# LightLink_V4.net
KiCad netlist of a schematic drawn in Altium Designer
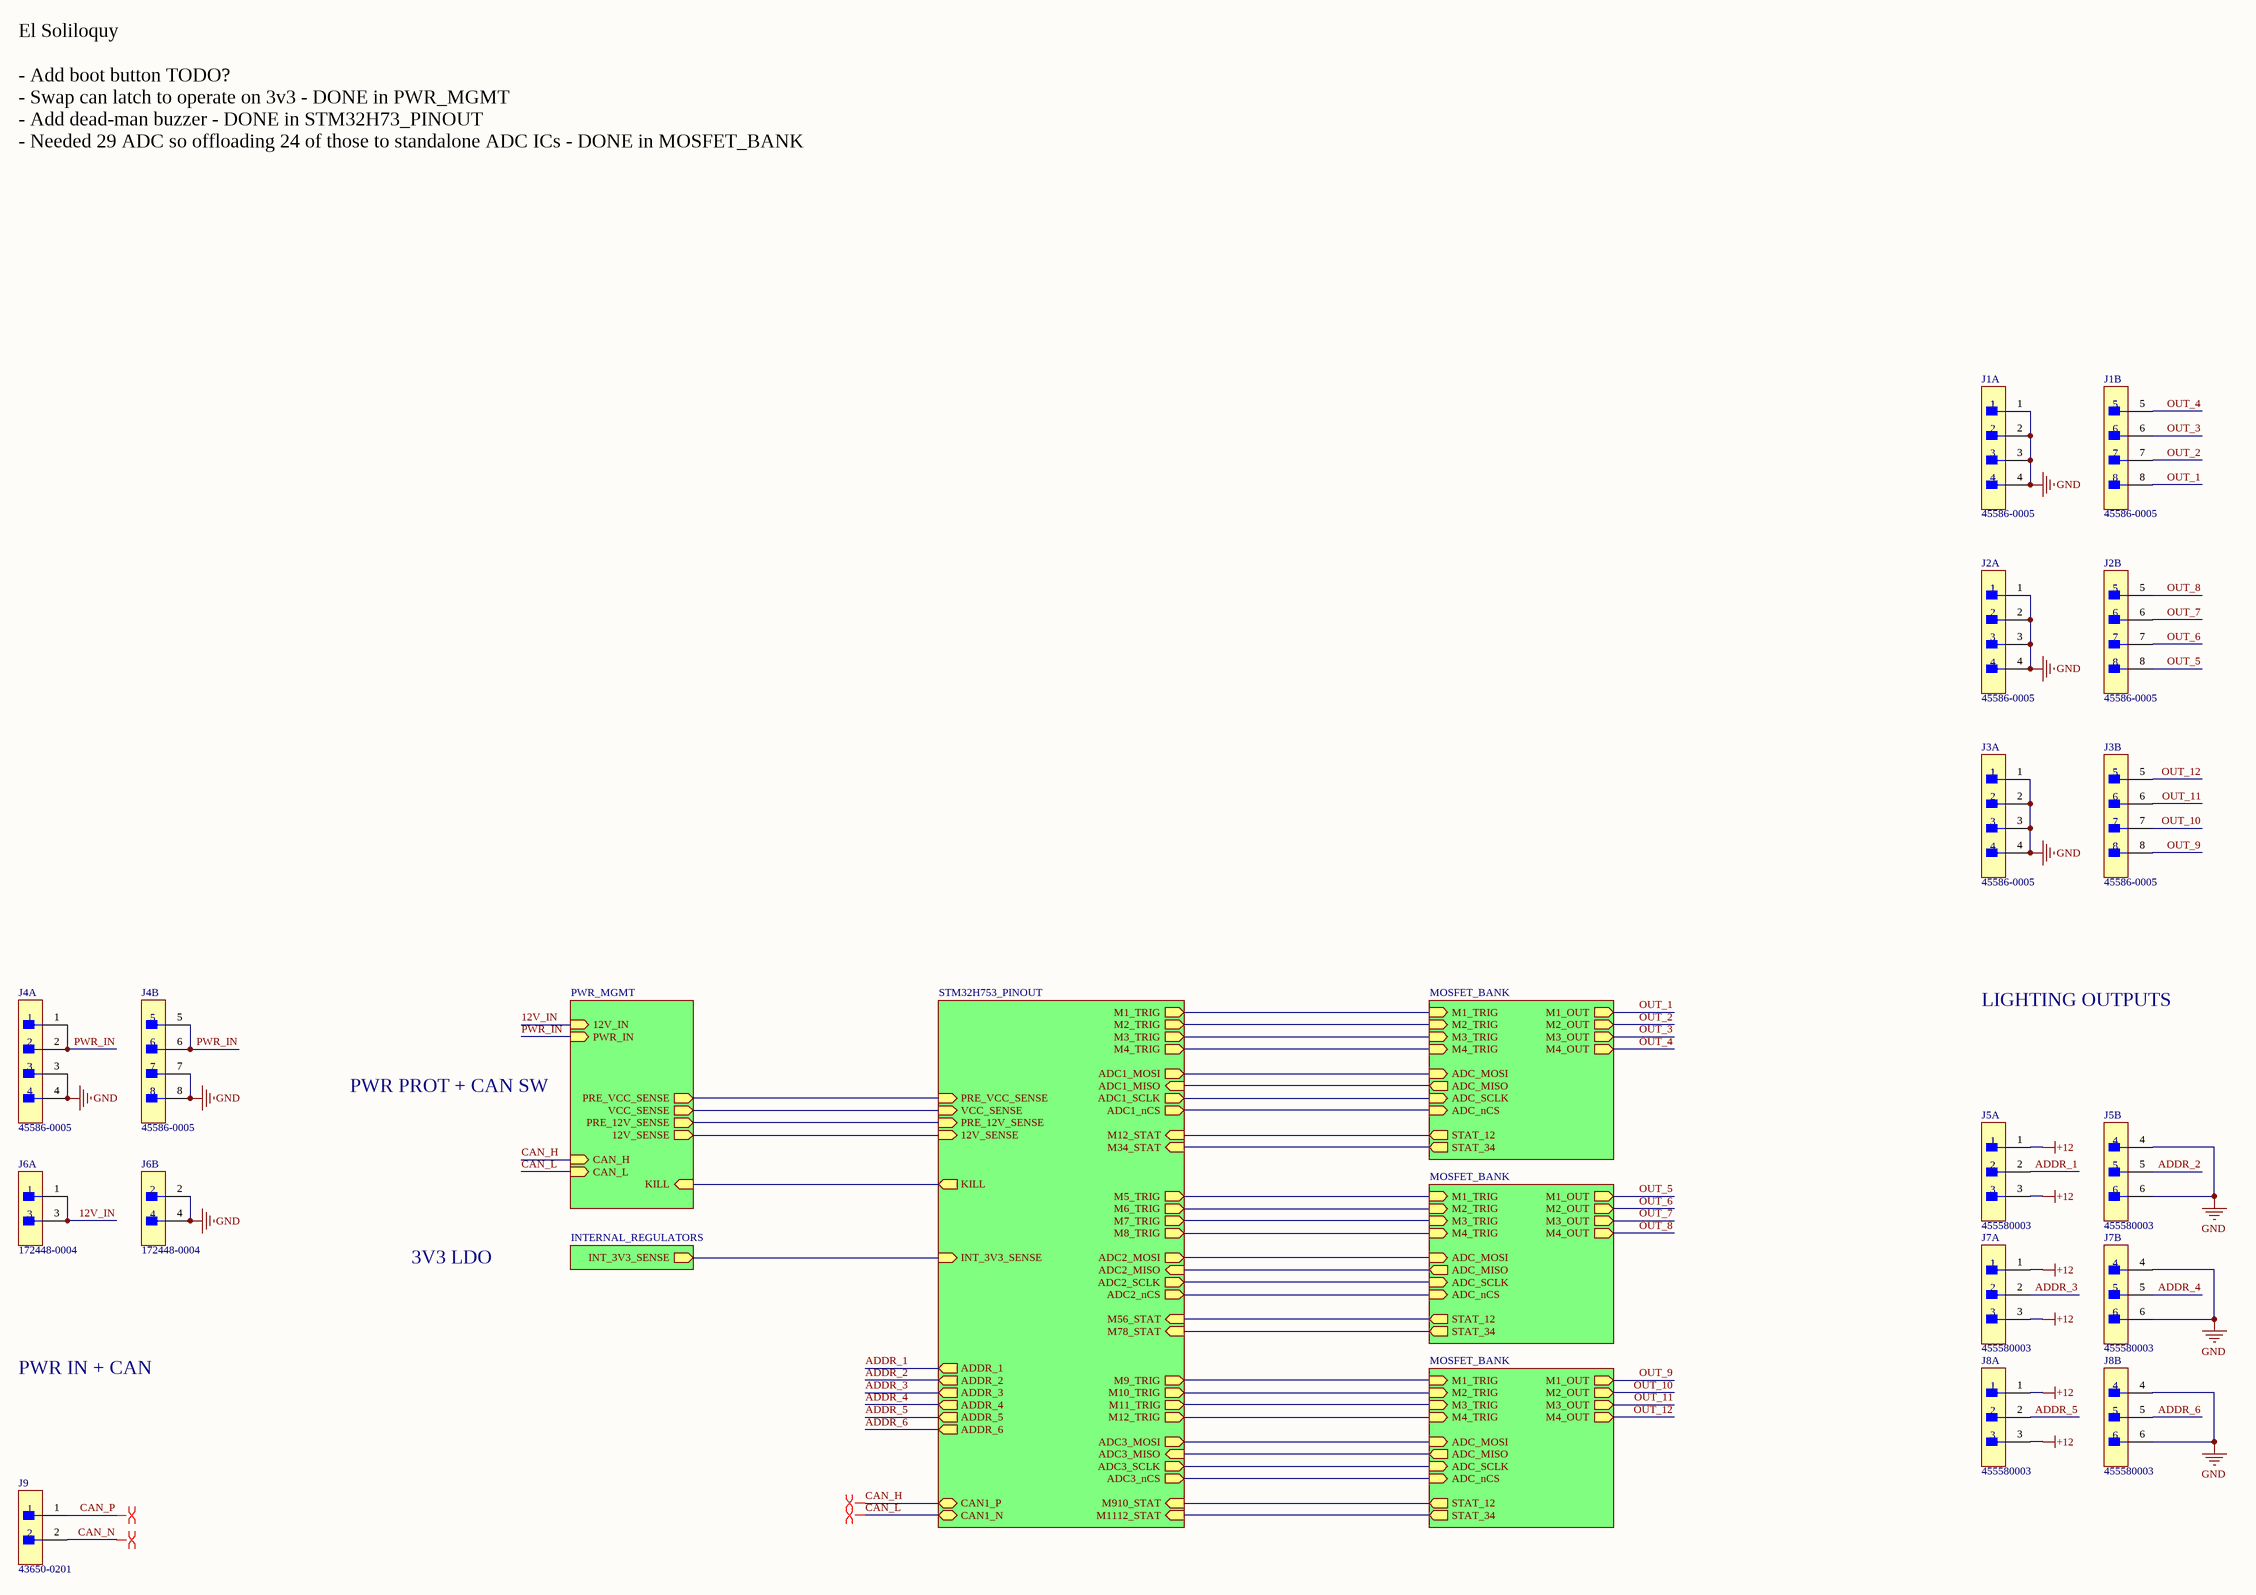
[diagram p0: LightLink_V4.SchDoc]

(export (version "E")
  (design (tool "Eeschema 10.0.6"))
  (components
    (comp (ref "J1")
      (value "45586-0005")
      (footprint "FP-45586-0005-MFG")
      (description "CONN HEADER R/A 8POS 4.2MM")
      (libsource (lib "Altium Content Vault") (part "85438c39ca9ef07d43bb2e97c52bc44"))
    )
    (comp (ref "J2")
      (value "45586-0005")
      (footprint "FP-45586-0005-MFG")
      (description "CONN HEADER R/A 8POS 4.2MM")
      (libsource (lib "Altium Content Vault") (part "85438c39ca9ef07d43bb2e97c52bc44"))
    )
    (comp (ref "J3")
      (value "45586-0005")
      (footprint "FP-45586-0005-MFG")
      (description "CONN HEADER R/A 8POS 4.2MM")
      (libsource (lib "Altium Content Vault") (part "85438c39ca9ef07d43bb2e97c52bc44"))
    )
    (comp (ref "J4")
      (value "45586-0005")
      (footprint "FP-45586-0005-MFG")
      (description "CONN HEADER R/A 8POS 4.2MM")
      (libsource (lib "Altium Content Vault") (part "85438c39ca9ef07d43bb2e97c52bc44"))
    )
    (comp (ref "J5")
      (value "455580003")
      (footprint "FP-455580003-MFG")
      (description "CONN HEADER R/A 6POS 4.2MM")
      (fields
        (field (name "OCTOPART") "https://octopart.com/45558-0003-molex-7672845")
        (field (name "MANUFACTURER") "Molex")
      )
      (libsource (lib "Altium Content Vault") (part "bb9cbdb24149a20ba329b4e86909569"))
    )
    (comp (ref "J6")
      (value "172448-0004")
      (footprint "FP-39-30-1041-MFG")
      (description "Different component but holes should line up. Original P/N is 39-30-1041")
      (fields
        (field (name "MANUFACTURER") "Molex")
        (field (name "OCTOPART") "https://octopart.com/39-30-1041-molex-276737")
      )
      (libsource (lib "Altium Content Vault") (part "1621473add15499e993d6bbd36d0f06"))
    )
    (comp (ref "J7")
      (value "455580003")
      (footprint "FP-455580003-MFG")
      (description "CONN HEADER R/A 6POS 4.2MM")
      (fields
        (field (name "OCTOPART") "https://octopart.com/45558-0003-molex-7672845")
        (field (name "MANUFACTURER") "Molex")
      )
      (libsource (lib "Altium Content Vault") (part "bb9cbdb24149a20ba329b4e86909569"))
    )
    (comp (ref "J8")
      (value "455580003")
      (footprint "FP-455580003-MFG")
      (description "CONN HEADER R/A 6POS 4.2MM")
      (fields
        (field (name "OCTOPART") "https://octopart.com/45558-0003-molex-7672845")
        (field (name "MANUFACTURER") "Molex")
      )
      (libsource (lib "Altium Content Vault") (part "bb9cbdb24149a20ba329b4e86909569"))
    )
    (comp (ref "J9")
      (value "43650-0201")
      (footprint "FP-43650-0201-MFG")
      (description "CONN HEADER R/A 2POS 3MM")
      (libsource (lib "Altium Content Vault") (part "3bc925449376181038e59eaffc5286c"))
    )
  )
  (nets
    (net (code "1") (name "+12") (class "Default")
      (node (ref "J5") (pin "1") (pinfunction "1_1") (pintype "passive"))
      (node (ref "J5") (pin "3") (pinfunction "3_3") (pintype "passive"))
      (node (ref "J7") (pin "1") (pinfunction "1_1") (pintype "passive"))
      (node (ref "J7") (pin "3") (pinfunction "3_3") (pintype "passive"))
      (node (ref "J8") (pin "1") (pinfunction "1_1") (pintype "passive"))
      (node (ref "J8") (pin "3") (pinfunction "3_3") (pintype "passive"))
    )
    (net (code "2") (name "/12V_IN") (class "Default")
      (node (ref "J6") (pin "1") (pinfunction "1_1") (pintype "passive"))
      (node (ref "J6") (pin "3") (pinfunction "3_3") (pintype "passive"))
    )
    (net (code "16") (name "/ADDR_1") (class "Default")
      (node (ref "J5") (pin "2") (pinfunction "2_2") (pintype "passive"))
    )
    (net (code "17") (name "/ADDR_2") (class "Default")
      (node (ref "J5") (pin "5") (pinfunction "5_5") (pintype "passive"))
    )
    (net (code "18") (name "/ADDR_3") (class "Default")
      (node (ref "J7") (pin "2") (pinfunction "2_2") (pintype "passive"))
    )
    (net (code "19") (name "/ADDR_4") (class "Default")
      (node (ref "J7") (pin "5") (pinfunction "5_5") (pintype "passive"))
    )
    (net (code "20") (name "/ADDR_5") (class "Default")
      (node (ref "J8") (pin "2") (pinfunction "2_2") (pintype "passive"))
    )
    (net (code "21") (name "/ADDR_6") (class "Default")
      (node (ref "J8") (pin "5") (pinfunction "5_5") (pintype "passive"))
    )
    (net (code "24") (name "/CAN_N") (class "Default")
      (node (ref "J9") (pin "2") (pinfunction "2_2") (pintype "passive"))
    )
    (net (code "25") (name "/CAN_P") (class "Default")
      (node (ref "J9") (pin "1") (pinfunction "1_1") (pintype "passive"))
    )
    (net (code "40") (name "/OUT_1") (class "Default")
      (node (ref "J1") (pin "8") (pinfunction "8_8") (pintype "passive"))
    )
    (net (code "41") (name "/OUT_2") (class "Default")
      (node (ref "J1") (pin "7") (pinfunction "7_7") (pintype "passive"))
    )
    (net (code "42") (name "/OUT_3") (class "Default")
      (node (ref "J1") (pin "6") (pinfunction "6_6") (pintype "passive"))
    )
    (net (code "43") (name "/OUT_4") (class "Default")
      (node (ref "J1") (pin "5") (pinfunction "5_5") (pintype "passive"))
    )
    (net (code "44") (name "/OUT_5") (class "Default")
      (node (ref "J2") (pin "8") (pinfunction "8_8") (pintype "passive"))
    )
    (net (code "45") (name "/OUT_6") (class "Default")
      (node (ref "J2") (pin "7") (pinfunction "7_7") (pintype "passive"))
    )
    (net (code "46") (name "/OUT_7") (class "Default")
      (node (ref "J2") (pin "6") (pinfunction "6_6") (pintype "passive"))
    )
    (net (code "47") (name "/OUT_8") (class "Default")
      (node (ref "J2") (pin "5") (pinfunction "5_5") (pintype "passive"))
    )
    (net (code "48") (name "/OUT_9") (class "Default")
      (node (ref "J3") (pin "8") (pinfunction "8_8") (pintype "passive"))
    )
    (net (code "49") (name "/OUT_10") (class "Default")
      (node (ref "J3") (pin "7") (pinfunction "7_7") (pintype "passive"))
    )
    (net (code "50") (name "/OUT_11") (class "Default")
      (node (ref "J3") (pin "6") (pinfunction "6_6") (pintype "passive"))
    )
    (net (code "51") (name "/OUT_12") (class "Default")
      (node (ref "J3") (pin "5") (pinfunction "5_5") (pintype "passive"))
    )
    (net (code "54") (name "/PWR_IN") (class "Default")
      (node (ref "J4") (pin "1") (pinfunction "1_1") (pintype "passive"))
      (node (ref "J4") (pin "2") (pinfunction "2_2") (pintype "passive"))
      (node (ref "J4") (pin "5") (pinfunction "5_5") (pintype "passive"))
      (node (ref "J4") (pin "6") (pinfunction "6_6") (pintype "passive"))
    )
    (net (code "62") (name "GND") (class "Default")
      (node (ref "J1") (pin "1") (pinfunction "1_1") (pintype "passive"))
      (node (ref "J1") (pin "2") (pinfunction "2_2") (pintype "passive"))
      (node (ref "J1") (pin "3") (pinfunction "3_3") (pintype "passive"))
      (node (ref "J1") (pin "4") (pinfunction "4_4") (pintype "passive"))
      (node (ref "J2") (pin "1") (pinfunction "1_1") (pintype "passive"))
      (node (ref "J2") (pin "2") (pinfunction "2_2") (pintype "passive"))
      (node (ref "J2") (pin "3") (pinfunction "3_3") (pintype "passive"))
      (node (ref "J2") (pin "4") (pinfunction "4_4") (pintype "passive"))
      (node (ref "J3") (pin "1") (pinfunction "1_1") (pintype "passive"))
      (node (ref "J3") (pin "2") (pinfunction "2_2") (pintype "passive"))
      (node (ref "J3") (pin "3") (pinfunction "3_3") (pintype "passive"))
      (node (ref "J3") (pin "4") (pinfunction "4_4") (pintype "passive"))
      (node (ref "J4") (pin "3") (pinfunction "3_3") (pintype "passive"))
      (node (ref "J4") (pin "4") (pinfunction "4_4") (pintype "passive"))
      (node (ref "J4") (pin "7") (pinfunction "7_7") (pintype "passive"))
      (node (ref "J4") (pin "8") (pinfunction "8_8") (pintype "passive"))
      (node (ref "J5") (pin "4") (pinfunction "4_4") (pintype "passive"))
      (node (ref "J5") (pin "6") (pinfunction "6_6") (pintype "passive"))
      (node (ref "J6") (pin "2") (pinfunction "2_2") (pintype "passive"))
      (node (ref "J6") (pin "4") (pinfunction "4_4") (pintype "passive"))
      (node (ref "J7") (pin "4") (pinfunction "4_4") (pintype "passive"))
      (node (ref "J7") (pin "6") (pinfunction "6_6") (pintype "passive"))
      (node (ref "J8") (pin "4") (pinfunction "4_4") (pintype "passive"))
      (node (ref "J8") (pin "6") (pinfunction "6_6") (pintype "passive"))
    )
  )
)
